# pc-bus.net
KiCad netlist of a schematic drawn in EAGLE
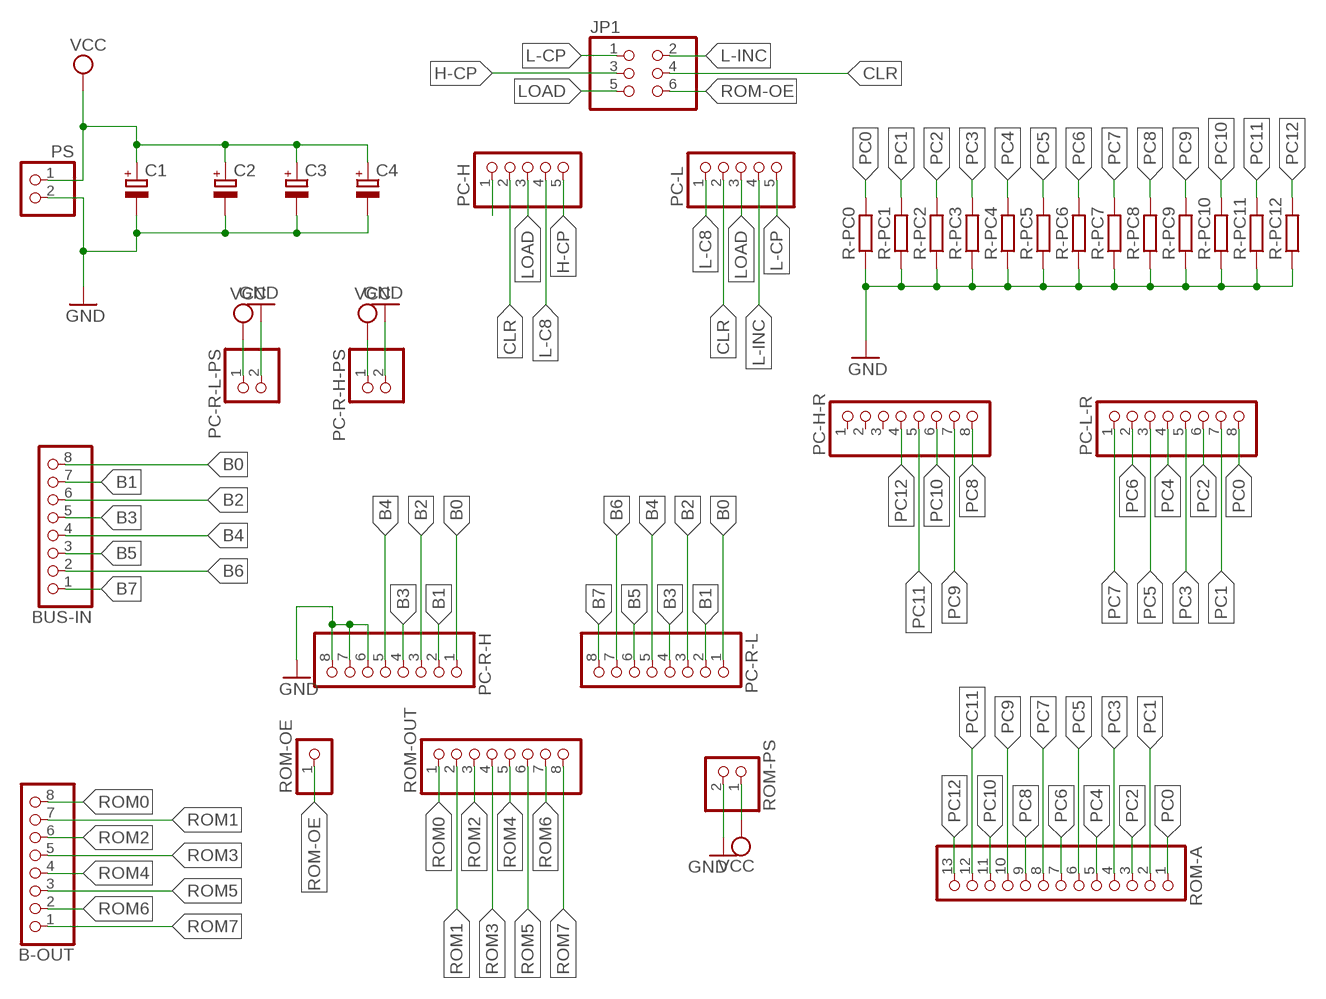
[diagram p0: schematic, sheet 1]

(export (version "E")
  (design (tool "Eeschema 10.0.6"))
  (components
    (comp (ref "B-OUT")
      (value "PINHD-1X8")
      (footprint "eagle-import:1X08")
      (libsource (lib "eagle-import") (part "PINHD-1X8"))
    )
    (comp (ref "BUS-IN")
      (value "PINHD-1X8")
      (footprint "eagle-import:1X08")
      (libsource (lib "eagle-import") (part "PINHD-1X8"))
    )
    (comp (ref "C1")
      (value "CPOL-EUE3.5-8")
      (footprint "eagle-import:E3,5-8")
      (libsource (lib "eagle-import") (part "CPOL-EUE3.5-8"))
    )
    (comp (ref "C2")
      (value "CPOL-EUE3.5-8")
      (footprint "eagle-import:E3,5-8")
      (libsource (lib "eagle-import") (part "CPOL-EUE3.5-8"))
    )
    (comp (ref "C3")
      (value "CPOL-EUE3.5-8")
      (footprint "eagle-import:E3,5-8")
      (libsource (lib "eagle-import") (part "CPOL-EUE3.5-8"))
    )
    (comp (ref "C4")
      (value "CPOL-EUE3.5-8")
      (footprint "eagle-import:E3,5-8")
      (libsource (lib "eagle-import") (part "CPOL-EUE3.5-8"))
    )
    (comp (ref "JP1")
      (value "PINHD-2X3")
      (footprint "eagle-import:2X03")
      (libsource (lib "eagle-import") (part "PINHD-2X3"))
    )
    (comp (ref "PC-H")
      (value "PINHD-1X5")
      (footprint "eagle-import:1X05")
      (libsource (lib "eagle-import") (part "PINHD-1X5"))
    )
    (comp (ref "PC-H-R")
      (value "PINHD-1X8")
      (footprint "eagle-import:1X08")
      (libsource (lib "eagle-import") (part "PINHD-1X8"))
    )
    (comp (ref "PC-L")
      (value "PINHD-1X5")
      (footprint "eagle-import:1X05")
      (libsource (lib "eagle-import") (part "PINHD-1X5"))
    )
    (comp (ref "PC-L-R")
      (value "PINHD-1X8")
      (footprint "eagle-import:1X08")
      (libsource (lib "eagle-import") (part "PINHD-1X8"))
    )
    (comp (ref "PC-R-H")
      (value "PINHD-1X8")
      (footprint "eagle-import:1X08")
      (libsource (lib "eagle-import") (part "PINHD-1X8"))
    )
    (comp (ref "PC-R-H-PS")
      (value "PINHD-1X2")
      (footprint "eagle-import:1X02")
      (libsource (lib "eagle-import") (part "PINHD-1X2"))
    )
    (comp (ref "PC-R-L")
      (value "PINHD-1X8")
      (footprint "eagle-import:1X08")
      (libsource (lib "eagle-import") (part "PINHD-1X8"))
    )
    (comp (ref "PC-R-L-PS")
      (value "PINHD-1X2")
      (footprint "eagle-import:1X02")
      (libsource (lib "eagle-import") (part "PINHD-1X2"))
    )
    (comp (ref "PS")
      (value "PINHD-1X2")
      (footprint "eagle-import:1X02")
      (libsource (lib "eagle-import") (part "PINHD-1X2"))
    )
    (comp (ref "R-PC0")
      (value "R-EU_0204/7")
      (footprint "eagle-import:0204_7")
      (libsource (lib "eagle-import") (part "R-EU_0204/7"))
    )
    (comp (ref "R-PC1")
      (value "R-EU_0204/7")
      (footprint "eagle-import:0204_7")
      (libsource (lib "eagle-import") (part "R-EU_0204/7"))
    )
    (comp (ref "R-PC2")
      (value "R-EU_0204/7")
      (footprint "eagle-import:0204_7")
      (libsource (lib "eagle-import") (part "R-EU_0204/7"))
    )
    (comp (ref "R-PC3")
      (value "R-EU_0204/7")
      (footprint "eagle-import:0204_7")
      (libsource (lib "eagle-import") (part "R-EU_0204/7"))
    )
    (comp (ref "R-PC4")
      (value "R-EU_0204/7")
      (footprint "eagle-import:0204_7")
      (libsource (lib "eagle-import") (part "R-EU_0204/7"))
    )
    (comp (ref "R-PC5")
      (value "R-EU_0204/7")
      (footprint "eagle-import:0204_7")
      (libsource (lib "eagle-import") (part "R-EU_0204/7"))
    )
    (comp (ref "R-PC6")
      (value "R-EU_0204/7")
      (footprint "eagle-import:0204_7")
      (libsource (lib "eagle-import") (part "R-EU_0204/7"))
    )
    (comp (ref "R-PC7")
      (value "R-EU_0204/7")
      (footprint "eagle-import:0204_7")
      (libsource (lib "eagle-import") (part "R-EU_0204/7"))
    )
    (comp (ref "R-PC8")
      (value "R-EU_0204/7")
      (footprint "eagle-import:0204_7")
      (libsource (lib "eagle-import") (part "R-EU_0204/7"))
    )
    (comp (ref "R-PC9")
      (value "R-EU_0204/7")
      (footprint "eagle-import:0204_7")
      (libsource (lib "eagle-import") (part "R-EU_0204/7"))
    )
    (comp (ref "R-PC10")
      (value "R-EU_0204/7")
      (footprint "eagle-import:0204_7")
      (libsource (lib "eagle-import") (part "R-EU_0204/7"))
    )
    (comp (ref "R-PC11")
      (value "R-EU_0204/7")
      (footprint "eagle-import:0204_7")
      (libsource (lib "eagle-import") (part "R-EU_0204/7"))
    )
    (comp (ref "R-PC12")
      (value "R-EU_0204/7")
      (footprint "eagle-import:0204_7")
      (libsource (lib "eagle-import") (part "R-EU_0204/7"))
    )
    (comp (ref "ROM-A")
      (value "PINHD-1X13")
      (footprint "eagle-import:1X13")
      (libsource (lib "eagle-import") (part "PINHD-1X13"))
    )
    (comp (ref "ROM-OE")
      (value "PINHD-1X1")
      (footprint "eagle-import:1X01")
      (libsource (lib "eagle-import") (part "PINHD-1X1"))
    )
    (comp (ref "ROM-OUT")
      (value "PINHD-1X8")
      (footprint "eagle-import:1X08")
      (libsource (lib "eagle-import") (part "PINHD-1X8"))
    )
    (comp (ref "ROM-PS")
      (value "PINHD-1X2")
      (footprint "eagle-import:1X02")
      (libsource (lib "eagle-import") (part "PINHD-1X2"))
    )
  )
  (nets
    (net (code "1") (name "B0") (class "Default")
      (node (ref "BUS-IN") (pin "8") (pinfunction "8_8") (pintype "passive"))
      (node (ref "PC-R-H") (pin "1") (pinfunction "1_1") (pintype "passive"))
      (node (ref "PC-R-L") (pin "1") (pinfunction "1_1") (pintype "passive"))
    )
    (net (code "2") (name "B1") (class "Default")
      (node (ref "BUS-IN") (pin "7") (pinfunction "7_7") (pintype "passive"))
      (node (ref "PC-R-H") (pin "2") (pinfunction "2_2") (pintype "passive"))
      (node (ref "PC-R-L") (pin "2") (pinfunction "2_2") (pintype "passive"))
    )
    (net (code "3") (name "B2") (class "Default")
      (node (ref "BUS-IN") (pin "6") (pinfunction "6_6") (pintype "passive"))
      (node (ref "PC-R-H") (pin "3") (pinfunction "3_3") (pintype "passive"))
      (node (ref "PC-R-L") (pin "3") (pinfunction "3_3") (pintype "passive"))
    )
    (net (code "4") (name "B3") (class "Default")
      (node (ref "BUS-IN") (pin "5") (pinfunction "5_5") (pintype "passive"))
      (node (ref "PC-R-H") (pin "4") (pinfunction "4_4") (pintype "passive"))
      (node (ref "PC-R-L") (pin "4") (pinfunction "4_4") (pintype "passive"))
    )
    (net (code "5") (name "B4") (class "Default")
      (node (ref "BUS-IN") (pin "4") (pinfunction "4_4") (pintype "passive"))
      (node (ref "PC-R-H") (pin "5") (pinfunction "5_5") (pintype "passive"))
      (node (ref "PC-R-L") (pin "5") (pinfunction "5_5") (pintype "passive"))
    )
    (net (code "6") (name "B5") (class "Default")
      (node (ref "BUS-IN") (pin "3") (pinfunction "3_3") (pintype "passive"))
      (node (ref "PC-R-L") (pin "6") (pinfunction "6_6") (pintype "passive"))
    )
    (net (code "7") (name "B6") (class "Default")
      (node (ref "BUS-IN") (pin "2") (pinfunction "2_2") (pintype "passive"))
      (node (ref "PC-R-L") (pin "7") (pinfunction "7_7") (pintype "passive"))
    )
    (net (code "8") (name "B7") (class "Default")
      (node (ref "BUS-IN") (pin "1") (pinfunction "1_1") (pintype "passive"))
      (node (ref "PC-R-L") (pin "8") (pinfunction "8_8") (pintype "passive"))
    )
    (net (code "9") (name "CLR") (class "Default")
      (node (ref "JP1") (pin "4") (pinfunction "4_4") (pintype "passive"))
      (node (ref "PC-H") (pin "2") (pinfunction "2_2") (pintype "passive"))
      (node (ref "PC-L") (pin "2") (pinfunction "2_2") (pintype "passive"))
    )
    (net (code "10") (name "GND") (class "Default")
      (node (ref "C1") (pin "-") (pinfunction "-_-") (pintype "passive"))
      (node (ref "C2") (pin "-") (pinfunction "-_-") (pintype "passive"))
      (node (ref "C3") (pin "-") (pinfunction "-_-") (pintype "passive"))
      (node (ref "C4") (pin "-") (pinfunction "-_-") (pintype "passive"))
      (node (ref "PC-R-H") (pin "6") (pinfunction "6_6") (pintype "passive"))
      (node (ref "PC-R-H") (pin "7") (pinfunction "7_7") (pintype "passive"))
      (node (ref "PC-R-H") (pin "8") (pinfunction "8_8") (pintype "passive"))
      (node (ref "PC-R-H-PS") (pin "2") (pinfunction "2_2") (pintype "passive"))
      (node (ref "PC-R-L-PS") (pin "2") (pinfunction "2_2") (pintype "passive"))
      (node (ref "PS") (pin "2") (pinfunction "2_2") (pintype "passive"))
      (node (ref "R-PC0") (pin "1") (pinfunction "1_1") (pintype "passive"))
      (node (ref "R-PC1") (pin "1") (pinfunction "1_1") (pintype "passive"))
      (node (ref "R-PC10") (pin "1") (pinfunction "1_1") (pintype "passive"))
      (node (ref "R-PC11") (pin "1") (pinfunction "1_1") (pintype "passive"))
      (node (ref "R-PC12") (pin "1") (pinfunction "1_1") (pintype "passive"))
      (node (ref "R-PC2") (pin "1") (pinfunction "1_1") (pintype "passive"))
      (node (ref "R-PC3") (pin "1") (pinfunction "1_1") (pintype "passive"))
      (node (ref "R-PC4") (pin "1") (pinfunction "1_1") (pintype "passive"))
      (node (ref "R-PC5") (pin "1") (pinfunction "1_1") (pintype "passive"))
      (node (ref "R-PC6") (pin "1") (pinfunction "1_1") (pintype "passive"))
      (node (ref "R-PC7") (pin "1") (pinfunction "1_1") (pintype "passive"))
      (node (ref "R-PC8") (pin "1") (pinfunction "1_1") (pintype "passive"))
      (node (ref "R-PC9") (pin "1") (pinfunction "1_1") (pintype "passive"))
      (node (ref "ROM-PS") (pin "2") (pinfunction "2_2") (pintype "passive"))
    )
    (net (code "11") (name "H-CP") (class "Default")
      (node (ref "JP1") (pin "3") (pinfunction "3_3") (pintype "passive"))
      (node (ref "PC-H") (pin "5") (pinfunction "5_5") (pintype "passive"))
    )
    (net (code "12") (name "L-C8") (class "Default")
      (node (ref "PC-H") (pin "4") (pinfunction "4_4") (pintype "passive"))
      (node (ref "PC-L") (pin "1") (pinfunction "1_1") (pintype "passive"))
    )
    (net (code "13") (name "L-CP") (class "Default")
      (node (ref "JP1") (pin "1") (pinfunction "1_1") (pintype "passive"))
      (node (ref "PC-L") (pin "5") (pinfunction "5_5") (pintype "passive"))
    )
    (net (code "14") (name "L-INC") (class "Default")
      (node (ref "JP1") (pin "2") (pinfunction "2_2") (pintype "passive"))
      (node (ref "PC-L") (pin "4") (pinfunction "4_4") (pintype "passive"))
    )
    (net (code "15") (name "LOAD") (class "Default")
      (node (ref "JP1") (pin "5") (pinfunction "5_5") (pintype "passive"))
      (node (ref "PC-H") (pin "3") (pinfunction "3_3") (pintype "passive"))
      (node (ref "PC-L") (pin "3") (pinfunction "3_3") (pintype "passive"))
    )
    (net (code "16") (name "PC0") (class "Default")
      (node (ref "PC-L-R") (pin "8") (pinfunction "8_8") (pintype "passive"))
      (node (ref "R-PC0") (pin "2") (pinfunction "2_2") (pintype "passive"))
      (node (ref "ROM-A") (pin "1") (pinfunction "1_1") (pintype "passive"))
    )
    (net (code "17") (name "PC1") (class "Default")
      (node (ref "PC-L-R") (pin "7") (pinfunction "7_7") (pintype "passive"))
      (node (ref "R-PC1") (pin "2") (pinfunction "2_2") (pintype "passive"))
      (node (ref "ROM-A") (pin "2") (pinfunction "2_2") (pintype "passive"))
    )
    (net (code "18") (name "PC2") (class "Default")
      (node (ref "PC-L-R") (pin "6") (pinfunction "6_6") (pintype "passive"))
      (node (ref "R-PC2") (pin "2") (pinfunction "2_2") (pintype "passive"))
      (node (ref "ROM-A") (pin "3") (pinfunction "3_3") (pintype "passive"))
    )
    (net (code "19") (name "PC3") (class "Default")
      (node (ref "PC-L-R") (pin "5") (pinfunction "5_5") (pintype "passive"))
      (node (ref "R-PC3") (pin "2") (pinfunction "2_2") (pintype "passive"))
      (node (ref "ROM-A") (pin "4") (pinfunction "4_4") (pintype "passive"))
    )
    (net (code "20") (name "PC4") (class "Default")
      (node (ref "PC-L-R") (pin "4") (pinfunction "4_4") (pintype "passive"))
      (node (ref "R-PC4") (pin "2") (pinfunction "2_2") (pintype "passive"))
      (node (ref "ROM-A") (pin "5") (pinfunction "5_5") (pintype "passive"))
    )
    (net (code "21") (name "PC5") (class "Default")
      (node (ref "PC-L-R") (pin "3") (pinfunction "3_3") (pintype "passive"))
      (node (ref "R-PC5") (pin "2") (pinfunction "2_2") (pintype "passive"))
      (node (ref "ROM-A") (pin "6") (pinfunction "6_6") (pintype "passive"))
    )
    (net (code "22") (name "PC6") (class "Default")
      (node (ref "PC-L-R") (pin "2") (pinfunction "2_2") (pintype "passive"))
      (node (ref "R-PC6") (pin "2") (pinfunction "2_2") (pintype "passive"))
      (node (ref "ROM-A") (pin "7") (pinfunction "7_7") (pintype "passive"))
    )
    (net (code "23") (name "PC7") (class "Default")
      (node (ref "PC-L-R") (pin "1") (pinfunction "1_1") (pintype "passive"))
      (node (ref "R-PC7") (pin "2") (pinfunction "2_2") (pintype "passive"))
      (node (ref "ROM-A") (pin "8") (pinfunction "8_8") (pintype "passive"))
    )
    (net (code "24") (name "PC8") (class "Default")
      (node (ref "PC-H-R") (pin "8") (pinfunction "8_8") (pintype "passive"))
      (node (ref "R-PC8") (pin "2") (pinfunction "2_2") (pintype "passive"))
      (node (ref "ROM-A") (pin "9") (pinfunction "9_9") (pintype "passive"))
    )
    (net (code "25") (name "PC9") (class "Default")
      (node (ref "PC-H-R") (pin "7") (pinfunction "7_7") (pintype "passive"))
      (node (ref "R-PC9") (pin "2") (pinfunction "2_2") (pintype "passive"))
      (node (ref "ROM-A") (pin "10") (pinfunction "10_10") (pintype "passive"))
    )
    (net (code "26") (name "PC10") (class "Default")
      (node (ref "PC-H-R") (pin "6") (pinfunction "6_6") (pintype "passive"))
      (node (ref "R-PC10") (pin "2") (pinfunction "2_2") (pintype "passive"))
      (node (ref "ROM-A") (pin "11") (pinfunction "11_11") (pintype "passive"))
    )
    (net (code "27") (name "PC11") (class "Default")
      (node (ref "PC-H-R") (pin "5") (pinfunction "5_5") (pintype "passive"))
      (node (ref "R-PC11") (pin "2") (pinfunction "2_2") (pintype "passive"))
      (node (ref "ROM-A") (pin "12") (pinfunction "12_12") (pintype "passive"))
    )
    (net (code "28") (name "PC12") (class "Default")
      (node (ref "PC-H-R") (pin "4") (pinfunction "4_4") (pintype "passive"))
      (node (ref "R-PC12") (pin "2") (pinfunction "2_2") (pintype "passive"))
      (node (ref "ROM-A") (pin "13") (pinfunction "13_13") (pintype "passive"))
    )
    (net (code "29") (name "ROM-OE") (class "Default")
      (node (ref "JP1") (pin "6") (pinfunction "6_6") (pintype "passive"))
      (node (ref "ROM-OE") (pin "1") (pinfunction "1_1") (pintype "passive"))
    )
    (net (code "30") (name "ROM0") (class "Default")
      (node (ref "B-OUT") (pin "8") (pinfunction "8_8") (pintype "passive"))
      (node (ref "ROM-OUT") (pin "1") (pinfunction "1_1") (pintype "passive"))
    )
    (net (code "31") (name "ROM1") (class "Default")
      (node (ref "B-OUT") (pin "7") (pinfunction "7_7") (pintype "passive"))
      (node (ref "ROM-OUT") (pin "2") (pinfunction "2_2") (pintype "passive"))
    )
    (net (code "32") (name "ROM2") (class "Default")
      (node (ref "B-OUT") (pin "6") (pinfunction "6_6") (pintype "passive"))
      (node (ref "ROM-OUT") (pin "3") (pinfunction "3_3") (pintype "passive"))
    )
    (net (code "33") (name "ROM3") (class "Default")
      (node (ref "B-OUT") (pin "5") (pinfunction "5_5") (pintype "passive"))
      (node (ref "ROM-OUT") (pin "4") (pinfunction "4_4") (pintype "passive"))
    )
    (net (code "34") (name "ROM4") (class "Default")
      (node (ref "B-OUT") (pin "4") (pinfunction "4_4") (pintype "passive"))
      (node (ref "ROM-OUT") (pin "5") (pinfunction "5_5") (pintype "passive"))
    )
    (net (code "35") (name "ROM5") (class "Default")
      (node (ref "B-OUT") (pin "3") (pinfunction "3_3") (pintype "passive"))
      (node (ref "ROM-OUT") (pin "6") (pinfunction "6_6") (pintype "passive"))
    )
    (net (code "36") (name "ROM6") (class "Default")
      (node (ref "B-OUT") (pin "2") (pinfunction "2_2") (pintype "passive"))
      (node (ref "ROM-OUT") (pin "7") (pinfunction "7_7") (pintype "passive"))
    )
    (net (code "37") (name "ROM7") (class "Default")
      (node (ref "B-OUT") (pin "1") (pinfunction "1_1") (pintype "passive"))
      (node (ref "ROM-OUT") (pin "8") (pinfunction "8_8") (pintype "passive"))
    )
    (net (code "38") (name "VCC") (class "Default")
      (node (ref "C1") (pin "+") (pinfunction "+_+") (pintype "passive"))
      (node (ref "C2") (pin "+") (pinfunction "+_+") (pintype "passive"))
      (node (ref "C3") (pin "+") (pinfunction "+_+") (pintype "passive"))
      (node (ref "C4") (pin "+") (pinfunction "+_+") (pintype "passive"))
      (node (ref "PC-R-H-PS") (pin "1") (pinfunction "1_1") (pintype "passive"))
      (node (ref "PC-R-L-PS") (pin "1") (pinfunction "1_1") (pintype "passive"))
      (node (ref "PS") (pin "1") (pinfunction "1_1") (pintype "passive"))
      (node (ref "ROM-PS") (pin "1") (pinfunction "1_1") (pintype "passive"))
    )
    (net (code "39") (name "unconnected-(PC-H-Pad1)") (class "Default")
      (node (ref "PC-H") (pin "1") (pinfunction "1_1") (pintype "passive"))
    )
    (net (code "40") (name "unconnected-(PC-H-R-Pad1)") (class "Default")
      (node (ref "PC-H-R") (pin "1") (pinfunction "1_1") (pintype "passive"))
    )
    (net (code "41") (name "unconnected-(PC-H-R-Pad2)") (class "Default")
      (node (ref "PC-H-R") (pin "2") (pinfunction "2_2") (pintype "passive"))
    )
    (net (code "42") (name "unconnected-(PC-H-R-Pad3)") (class "Default")
      (node (ref "PC-H-R") (pin "3") (pinfunction "3_3") (pintype "passive"))
    )
  )
)
